# Logic_Analyzer.net
KiCad netlist of a schematic drawn in Altium Designer
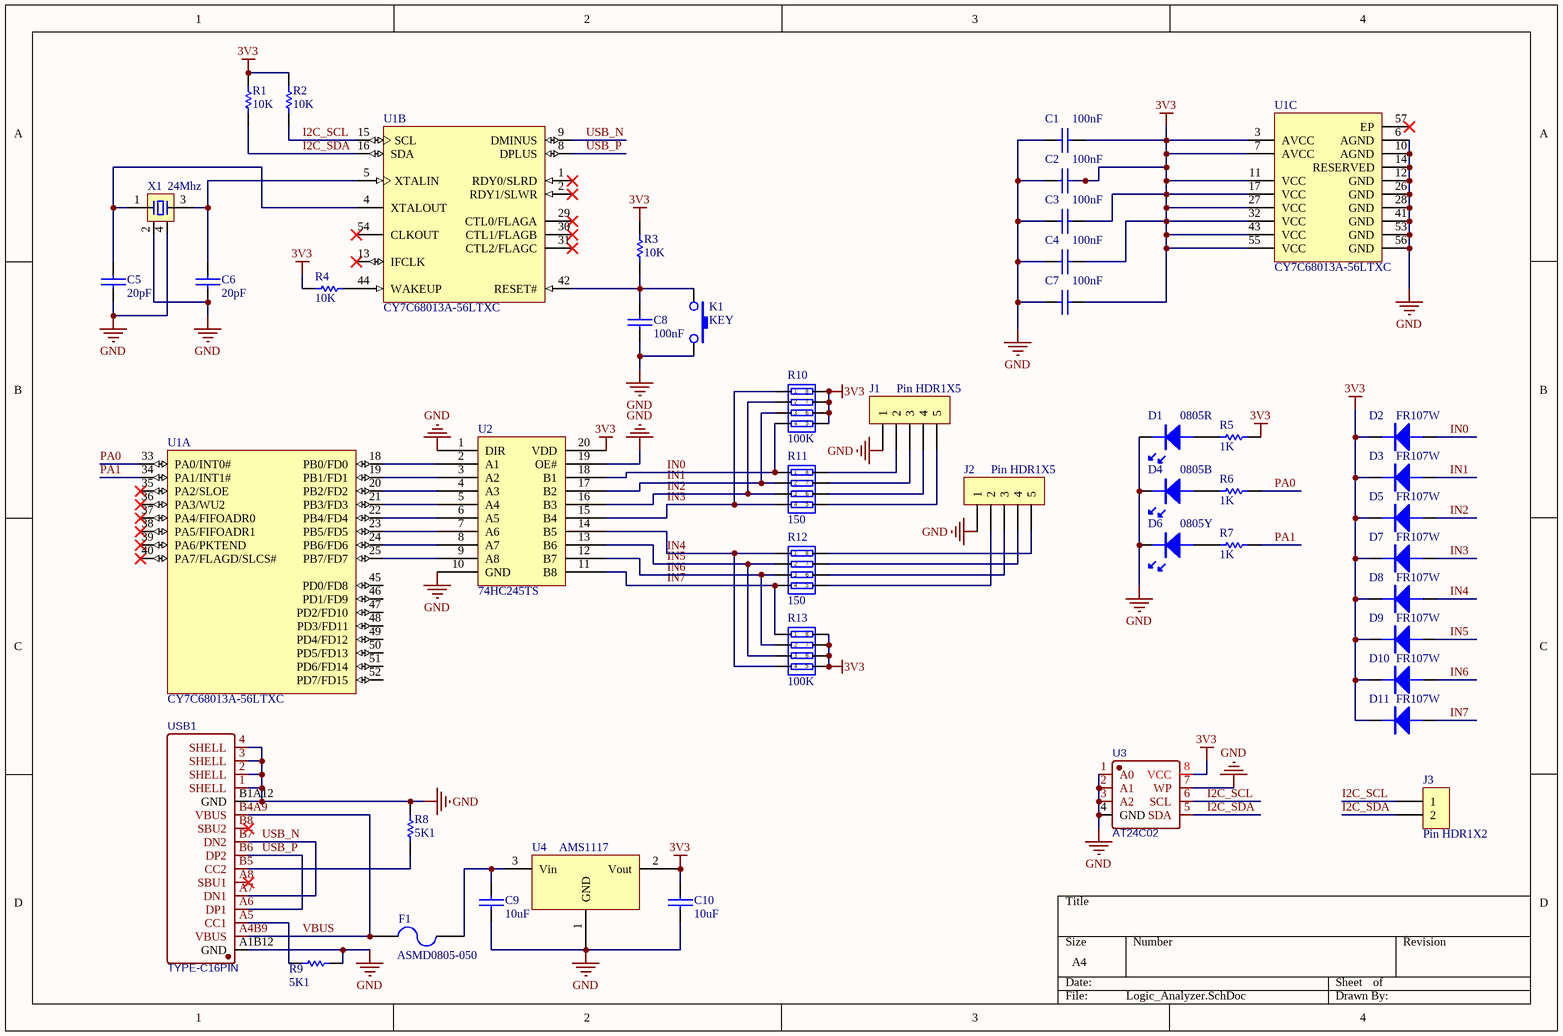
[diagram p0: Logic_Analyzer.SchDoc]

(export (version "E")
  (design (tool "Eeschema 10.0.6"))
  (components
    (comp (ref "C1")
      (value "100nF")
      (footprint "0603C")
      (description "无极性电容")
      (libsource (lib "电容") (part "CAP"))
    )
    (comp (ref "C2")
      (value "100nF")
      (footprint "0603C")
      (description "无极性电容")
      (libsource (lib "电容") (part "CAP"))
    )
    (comp (ref "C3")
      (value "100nF")
      (footprint "0603C")
      (description "无极性电容")
      (libsource (lib "电容") (part "CAP"))
    )
    (comp (ref "C4")
      (value "100nF")
      (footprint "0603C")
      (description "无极性电容")
      (libsource (lib "电容") (part "CAP"))
    )
    (comp (ref "C5")
      (value "20pF")
      (footprint "0603C")
      (description "无极性电容")
      (libsource (lib "电容") (part "CAP"))
    )
    (comp (ref "C6")
      (value "20pF")
      (footprint "0603C")
      (description "无极性电容")
      (libsource (lib "电容") (part "CAP"))
    )
    (comp (ref "C7")
      (value "100nF")
      (footprint "0603C")
      (description "无极性电容")
      (libsource (lib "电容") (part "CAP"))
    )
    (comp (ref "C8")
      (value "100nF")
      (footprint "0603C")
      (description "无极性电容")
      (libsource (lib "电容") (part "CAP"))
    )
    (comp (ref "C9")
      (value "10uF")
      (footprint "0603C")
      (description "无极性电容")
      (libsource (lib "电容") (part "CAP"))
    )
    (comp (ref "C10")
      (value "10uF")
      (footprint "0603C")
      (description "无极性电容")
      (libsource (lib "电容") (part "CAP"))
    )
    (comp (ref "D1") (value "0805R") (footprint "LED-0805R") (libsource (lib "LED") (part "LED")))
    (comp (ref "D2")
      (value "FR107W")
      (footprint "SOD-123")
      (description "普通二极管")
      (libsource (lib "二极管") (part "DIODE"))
    )
    (comp (ref "D3")
      (value "FR107W")
      (footprint "SOD-123")
      (description "普通二极管")
      (libsource (lib "二极管") (part "DIODE"))
    )
    (comp (ref "D4") (value "0805B") (footprint "LED-0805B") (libsource (lib "LED") (part "LED")))
    (comp (ref "D5")
      (value "FR107W")
      (footprint "SOD-123")
      (description "普通二极管")
      (libsource (lib "二极管") (part "DIODE"))
    )
    (comp (ref "D6") (value "0805Y") (footprint "LED-0805Y") (libsource (lib "LED") (part "LED")))
    (comp (ref "D7")
      (value "FR107W")
      (footprint "SOD-123")
      (description "普通二极管")
      (libsource (lib "二极管") (part "DIODE"))
    )
    (comp (ref "D8")
      (value "FR107W")
      (footprint "SOD-123")
      (description "普通二极管")
      (libsource (lib "二极管") (part "DIODE"))
    )
    (comp (ref "D9")
      (value "FR107W")
      (footprint "SOD-123")
      (description "普通二极管")
      (libsource (lib "二极管") (part "DIODE"))
    )
    (comp (ref "D10")
      (value "FR107W")
      (footprint "SOD-123")
      (description "普通二极管")
      (libsource (lib "二极管") (part "DIODE"))
    )
    (comp (ref "D11")
      (value "FR107W")
      (footprint "SOD-123")
      (description "普通二极管")
      (libsource (lib "二极管") (part "DIODE"))
    )
    (comp (ref "F1") (value "ASMD0805-050") (footprint "FUSE-0805") (libsource (lib "保险丝") (part "FUSE")))
    (comp (ref "J1")
      (value "Pin HDR1X5")
      (footprint "Pin HDR1X5/2.54mm-S-SMD")
      (libsource (lib "排针") (part "Pin HDR1X5"))
    )
    (comp (ref "J2")
      (value "Pin HDR1X5")
      (footprint "Pin HDR1X5/2.54mm-S-SMD")
      (libsource (lib "排针") (part "Pin HDR1X5"))
    )
    (comp (ref "J3")
      (value "Pin HDR1X2")
      (footprint "Pin HDR1X2/2.54mm-S")
      (libsource (lib "排针") (part "Pin HDR1X2"))
    )
    (comp (ref "K1")
      (value "KEY")
      (footprint "SW-SMD_L4.0-W2.9-P4.15-EH")
      (libsource (lib "轻触开关") (part "KEY"))
    )
    (comp (ref "R1") (value "10K") (footprint "0603R") (libsource (lib "电阻") (part "RES")))
    (comp (ref "R2") (value "10K") (footprint "0603R") (libsource (lib "电阻") (part "RES")))
    (comp (ref "R3") (value "10K") (footprint "0603R") (libsource (lib "电阻") (part "RES")))
    (comp (ref "R4") (value "10K") (footprint "0603R") (libsource (lib "电阻") (part "RES")))
    (comp (ref "R5") (value "1K") (footprint "0603R") (libsource (lib "电阻") (part "RES")))
    (comp (ref "R6") (value "1K") (footprint "0603R") (libsource (lib "电阻") (part "RES")))
    (comp (ref "R7") (value "1K") (footprint "0603R") (libsource (lib "电阻") (part "RES")))
    (comp (ref "R8") (value "5K1") (footprint "0603R") (libsource (lib "电阻") (part "RES")))
    (comp (ref "R9") (value "5K1") (footprint "0603R") (libsource (lib "电阻") (part "RES")))
    (comp (ref "R10")
      (value "100K")
      (footprint "RES-ARRAY-SMD_0603-8P-L3.2-W1.6-BL")
      (description "网络排阻4R")
      (libsource (lib "电阻") (part "RES_ARRAY*4"))
    )
    (comp (ref "R11")
      (value "150")
      (footprint "RES-ARRAY-SMD_0603-8P-L3.2-W1.6-BL")
      (description "网络排阻4R")
      (libsource (lib "电阻") (part "RES_ARRAY*4"))
    )
    (comp (ref "R12")
      (value "150")
      (footprint "RES-ARRAY-SMD_0603-8P-L3.2-W1.6-BL")
      (description "网络排阻4R")
      (libsource (lib "电阻") (part "RES_ARRAY*4"))
    )
    (comp (ref "R13")
      (value "100K")
      (footprint "RES-ARRAY-SMD_0603-8P-L3.2-W1.6-BL")
      (description "网络排阻4R")
      (libsource (lib "电阻") (part "RES_ARRAY*4"))
    )
    (comp (ref "U1")
      (value "CY7C68013A-56LTXC")
      (footprint "CYP-LTX56-5200X4500TP_M")
      (fields (field (name "MANUFACTURER") "Cypress"))
      (libsource (lib "Cypress USB Controllers") (part "CY7C68013A-56LTXC"))
    )
    (comp (ref "U2") (value "74HC245TS") (footprint "TSSOP20") (libsource (lib "74系列芯片") (part "74HC245TS")))
    (comp (ref "U3")
      (value "AT24C02")
      (footprint "SOP8")
      (fields (field (name "BOM_SUPPLIER PART") "C688857") (field (name "CONTRIBUTOR") "LCSC"))
      (libsource (lib "未分类IC") (part "AT24C02"))
    )
    (comp (ref "U4")
      (value "AMS1117")
      (footprint "SOT223")
      (description "三端稳压芯片")
      (libsource (lib "电源芯片") (part "AMS1117"))
    )
    (comp (ref "USB1")
      (value "TYPE-C16PIN")
      (footprint "USB-C-SMD_TYPE-C16PIN")
      (fields (field (name "BOM_SUPPLIER PART") "C393939") (field (name "CONTRIBUTOR") "LCSC"))
      (libsource (lib "USB") (part "USB-C_16PIN"))
    )
    (comp (ref "X1")
      (value "24Mhz")
      (footprint "OSC 3225-4P")
      (description "4脚无源晶振")
      (libsource (lib "晶振") (part "XTAL-4P"))
    )
  )
  (nets
    (net (code "1") (name "/I2C_SCL") (class "Default")
      (node (ref "J3") (pin "1") (pinfunction "1_1") (pintype "passive"))
      (node (ref "R2") (pin "1") (pinfunction "1_1") (pintype "passive"))
      (node (ref "U1") (pin "15") (pinfunction "SCL_15") (pintype "bidirectional"))
      (node (ref "U3") (pin "6") (pinfunction "SCL_6") (pintype "passive"))
    )
    (net (code "2") (name "/I2C_SDA") (class "Default")
      (node (ref "J3") (pin "2") (pinfunction "2_2") (pintype "passive"))
      (node (ref "R1") (pin "1") (pinfunction "1_1") (pintype "passive"))
      (node (ref "U1") (pin "16") (pinfunction "SDA_16") (pintype "bidirectional"))
      (node (ref "U3") (pin "5") (pinfunction "SDA_5") (pintype "passive"))
    )
    (net (code "3") (name "/IN0") (class "Default")
      (node (ref "D2") (pin "A") (pinfunction "A_A") (pintype "passive"))
      (node (ref "R10") (pin "4") (pinfunction "4_4") (pintype "passive"))
      (node (ref "R11") (pin "1") (pinfunction "1_1") (pintype "passive"))
      (node (ref "U2") (pin "18") (pinfunction "B1_18") (pintype "passive"))
    )
    (net (code "4") (name "/IN1") (class "Default")
      (node (ref "D3") (pin "A") (pinfunction "A_A") (pintype "passive"))
      (node (ref "R10") (pin "3") (pinfunction "3_3") (pintype "passive"))
      (node (ref "R11") (pin "2") (pinfunction "2_2") (pintype "passive"))
      (node (ref "U2") (pin "17") (pinfunction "B2_17") (pintype "passive"))
    )
    (net (code "5") (name "/IN2") (class "Default")
      (node (ref "D5") (pin "A") (pinfunction "A_A") (pintype "passive"))
      (node (ref "R10") (pin "2") (pinfunction "2_2") (pintype "passive"))
      (node (ref "R11") (pin "3") (pinfunction "3_3") (pintype "passive"))
      (node (ref "U2") (pin "16") (pinfunction "B3_16") (pintype "passive"))
    )
    (net (code "6") (name "/IN3") (class "Default")
      (node (ref "D7") (pin "A") (pinfunction "A_A") (pintype "passive"))
      (node (ref "R10") (pin "1") (pinfunction "1_1") (pintype "passive"))
      (node (ref "R11") (pin "4") (pinfunction "4_4") (pintype "passive"))
      (node (ref "U2") (pin "15") (pinfunction "B4_15") (pintype "passive"))
    )
    (net (code "7") (name "/IN4") (class "Default")
      (node (ref "D8") (pin "A") (pinfunction "A_A") (pintype "passive"))
      (node (ref "R12") (pin "1") (pinfunction "1_1") (pintype "passive"))
      (node (ref "R13") (pin "4") (pinfunction "4_4") (pintype "passive"))
      (node (ref "U2") (pin "14") (pinfunction "B5_14") (pintype "passive"))
    )
    (net (code "8") (name "/IN5") (class "Default")
      (node (ref "D9") (pin "A") (pinfunction "A_A") (pintype "passive"))
      (node (ref "R12") (pin "2") (pinfunction "2_2") (pintype "passive"))
      (node (ref "R13") (pin "3") (pinfunction "3_3") (pintype "passive"))
      (node (ref "U2") (pin "13") (pinfunction "B6_13") (pintype "passive"))
    )
    (net (code "9") (name "/IN6") (class "Default")
      (node (ref "D10") (pin "A") (pinfunction "A_A") (pintype "passive"))
      (node (ref "R12") (pin "3") (pinfunction "3_3") (pintype "passive"))
      (node (ref "R13") (pin "2") (pinfunction "2_2") (pintype "passive"))
      (node (ref "U2") (pin "12") (pinfunction "B7_12") (pintype "passive"))
    )
    (net (code "10") (name "/IN7") (class "Default")
      (node (ref "D11") (pin "A") (pinfunction "A_A") (pintype "passive"))
      (node (ref "R12") (pin "4") (pinfunction "4_4") (pintype "passive"))
      (node (ref "R13") (pin "1") (pinfunction "1_1") (pintype "passive"))
      (node (ref "U2") (pin "11") (pinfunction "B8_11") (pintype "passive"))
    )
    (net (code "11") (name "/PA0") (class "Default")
      (node (ref "R6") (pin "1") (pinfunction "1_1") (pintype "passive"))
      (node (ref "U1") (pin "33") (pinfunction "PA0/INT0#_33") (pintype "bidirectional"))
    )
    (net (code "12") (name "/PA1") (class "Default")
      (node (ref "R7") (pin "1") (pinfunction "1_1") (pintype "passive"))
      (node (ref "U1") (pin "34") (pinfunction "PA1/INT1#_34") (pintype "bidirectional"))
    )
    (net (code "13") (name "/USB_N") (class "Default")
      (node (ref "U1") (pin "9") (pinfunction "DMINUS_9") (pintype "bidirectional"))
      (node (ref "USB1") (pin "A7") (pinfunction "DN1_A7") (pintype "passive"))
      (node (ref "USB1") (pin "B7") (pinfunction "DN2_B7") (pintype "passive"))
    )
    (net (code "14") (name "/USB_P") (class "Default")
      (node (ref "U1") (pin "8") (pinfunction "DPLUS_8") (pintype "bidirectional"))
      (node (ref "USB1") (pin "A6") (pinfunction "DP1_A6") (pintype "passive"))
      (node (ref "USB1") (pin "B6") (pinfunction "DP2_B6") (pintype "passive"))
    )
    (net (code "15") (name "/VBUS") (class "Default")
      (node (ref "F1") (pin "1") (pinfunction "1_1") (pintype "passive"))
      (node (ref "USB1") (pin "A4B9") (pinfunction "VBUS_A4B9") (pintype "passive"))
      (node (ref "USB1") (pin "B4A9") (pinfunction "VBUS_B4A9") (pintype "passive"))
    )
    (net (code "16") (name "3V3") (class "Default")
      (node (ref "C1") (pin "1") (pinfunction "1_1") (pintype "passive"))
      (node (ref "C10") (pin "2") (pinfunction "2_2") (pintype "passive"))
      (node (ref "C2") (pin "1") (pinfunction "1_1") (pintype "passive"))
      (node (ref "C3") (pin "1") (pinfunction "1_1") (pintype "passive"))
      (node (ref "C4") (pin "1") (pinfunction "1_1") (pintype "passive"))
      (node (ref "C7") (pin "1") (pinfunction "1_1") (pintype "passive"))
      (node (ref "D10") (pin "K") (pinfunction "K_K") (pintype "passive"))
      (node (ref "D11") (pin "K") (pinfunction "K_K") (pintype "passive"))
      (node (ref "D2") (pin "K") (pinfunction "K_K") (pintype "passive"))
      (node (ref "D3") (pin "K") (pinfunction "K_K") (pintype "passive"))
      (node (ref "D5") (pin "K") (pinfunction "K_K") (pintype "passive"))
      (node (ref "D7") (pin "K") (pinfunction "K_K") (pintype "passive"))
      (node (ref "D8") (pin "K") (pinfunction "K_K") (pintype "passive"))
      (node (ref "D9") (pin "K") (pinfunction "K_K") (pintype "passive"))
      (node (ref "R1") (pin "2") (pinfunction "2_2") (pintype "passive"))
      (node (ref "R10") (pin "5") (pinfunction "5_5") (pintype "passive"))
      (node (ref "R10") (pin "6") (pinfunction "6_6") (pintype "passive"))
      (node (ref "R10") (pin "7") (pinfunction "7_7") (pintype "passive"))
      (node (ref "R10") (pin "8") (pinfunction "8_8") (pintype "passive"))
      (node (ref "R13") (pin "5") (pinfunction "5_5") (pintype "passive"))
      (node (ref "R13") (pin "6") (pinfunction "6_6") (pintype "passive"))
      (node (ref "R13") (pin "7") (pinfunction "7_7") (pintype "passive"))
      (node (ref "R13") (pin "8") (pinfunction "8_8") (pintype "passive"))
      (node (ref "R2") (pin "2") (pinfunction "2_2") (pintype "passive"))
      (node (ref "R3") (pin "2") (pinfunction "2_2") (pintype "passive"))
      (node (ref "R4") (pin "2") (pinfunction "2_2") (pintype "passive"))
      (node (ref "R5") (pin "1") (pinfunction "1_1") (pintype "passive"))
      (node (ref "U1") (pin "11") (pinfunction "VCC_11") (pintype "power_in"))
      (node (ref "U1") (pin "17") (pinfunction "VCC_17") (pintype "power_in"))
      (node (ref "U1") (pin "27") (pinfunction "VCC_27") (pintype "power_in"))
      (node (ref "U1") (pin "3") (pinfunction "AVCC_3") (pintype "power_in"))
      (node (ref "U1") (pin "32") (pinfunction "VCC_32") (pintype "power_in"))
      (node (ref "U1") (pin "43") (pinfunction "VCC_43") (pintype "power_in"))
      (node (ref "U1") (pin "55") (pinfunction "VCC_55") (pintype "power_in"))
      (node (ref "U1") (pin "7") (pinfunction "AVCC_7") (pintype "power_in"))
      (node (ref "U2") (pin "20") (pinfunction "VDD_20") (pintype "passive"))
      (node (ref "U3") (pin "8") (pinfunction "VCC_8") (pintype "passive"))
      (node (ref "U4") (pin "2") (pinfunction "Vout_2") (pintype "passive"))
    )
    (net (code "17") (name "GND") (class "Default")
      (node (ref "C1") (pin "2") (pinfunction "2_2") (pintype "passive"))
      (node (ref "C10") (pin "1") (pinfunction "1_1") (pintype "passive"))
      (node (ref "C2") (pin "2") (pinfunction "2_2") (pintype "passive"))
      (node (ref "C3") (pin "2") (pinfunction "2_2") (pintype "passive"))
      (node (ref "C4") (pin "2") (pinfunction "2_2") (pintype "passive"))
      (node (ref "C5") (pin "1") (pinfunction "1_1") (pintype "passive"))
      (node (ref "C6") (pin "1") (pinfunction "1_1") (pintype "passive"))
      (node (ref "C7") (pin "2") (pinfunction "2_2") (pintype "passive"))
      (node (ref "C8") (pin "1") (pinfunction "1_1") (pintype "passive"))
      (node (ref "C9") (pin "1") (pinfunction "1_1") (pintype "passive"))
      (node (ref "D1") (pin "K") (pinfunction "K_K") (pintype "passive"))
      (node (ref "D4") (pin "K") (pinfunction "K_K") (pintype "passive"))
      (node (ref "D6") (pin "K") (pinfunction "K_K") (pintype "passive"))
      (node (ref "J1") (pin "1") (pinfunction "1_1") (pintype "passive"))
      (node (ref "J2") (pin "1") (pinfunction "1_1") (pintype "passive"))
      (node (ref "K1") (pin "3") (pinfunction "3_3") (pintype "passive"))
      (node (ref "R8") (pin "1") (pinfunction "1_1") (pintype "passive"))
      (node (ref "R9") (pin "1") (pinfunction "1_1") (pintype "passive"))
      (node (ref "U1") (pin "10") (pinfunction "AGND_10") (pintype "power_in"))
      (node (ref "U1") (pin "12") (pinfunction "GND_12") (pintype "power_in"))
      (node (ref "U1") (pin "14") (pinfunction "RESERVED_14") (pintype "power_in"))
      (node (ref "U1") (pin "26") (pinfunction "GND_26") (pintype "power_in"))
      (node (ref "U1") (pin "28") (pinfunction "GND_28") (pintype "power_in"))
      (node (ref "U1") (pin "41") (pinfunction "GND_41") (pintype "power_in"))
      (node (ref "U1") (pin "53") (pinfunction "GND_53") (pintype "power_in"))
      (node (ref "U1") (pin "56") (pinfunction "GND_56") (pintype "power_in"))
      (node (ref "U1") (pin "6") (pinfunction "AGND_6") (pintype "power_in"))
      (node (ref "U2") (pin "1") (pinfunction "DIR_1") (pintype "passive"))
      (node (ref "U2") (pin "10") (pinfunction "GND_10") (pintype "passive"))
      (node (ref "U2") (pin "19") (pinfunction "OE#_19") (pintype "passive"))
      (node (ref "U3") (pin "1") (pinfunction "A0_1") (pintype "passive"))
      (node (ref "U3") (pin "2") (pinfunction "A1_2") (pintype "passive"))
      (node (ref "U3") (pin "3") (pinfunction "A2_3") (pintype "passive"))
      (node (ref "U3") (pin "4") (pinfunction "GND_4") (pintype "passive"))
      (node (ref "U3") (pin "7") (pinfunction "WP_7") (pintype "passive"))
      (node (ref "U4") (pin "1") (pinfunction "GND_1") (pintype "passive"))
      (node (ref "USB1") (pin "1") (pinfunction "SHELL_1") (pintype "passive"))
      (node (ref "USB1") (pin "2") (pinfunction "SHELL_2") (pintype "passive"))
      (node (ref "USB1") (pin "3") (pinfunction "SHELL_3") (pintype "passive"))
      (node (ref "USB1") (pin "4") (pinfunction "SHELL_4") (pintype "passive"))
      (node (ref "USB1") (pin "A1B12") (pinfunction "GND_A1B12") (pintype "passive"))
      (node (ref "USB1") (pin "B1A12") (pinfunction "GND_B1A12") (pintype "passive"))
      (node (ref "X1") (pin "2") (pinfunction "2_2") (pintype "passive"))
      (node (ref "X1") (pin "4") (pinfunction "4_4") (pintype "passive"))
    )
    (net (code "18") (name "Net-(D1-PadA)") (class "Default")
      (node (ref "D1") (pin "A") (pinfunction "A_A") (pintype "passive"))
      (node (ref "R5") (pin "2") (pinfunction "2_2") (pintype "passive"))
    )
    (net (code "19") (name "Net-(D4-PadA)") (class "Default")
      (node (ref "D4") (pin "A") (pinfunction "A_A") (pintype "passive"))
      (node (ref "R6") (pin "2") (pinfunction "2_2") (pintype "passive"))
    )
    (net (code "20") (name "Net-(D6-PadA)") (class "Default")
      (node (ref "D6") (pin "A") (pinfunction "A_A") (pintype "passive"))
      (node (ref "R7") (pin "2") (pinfunction "2_2") (pintype "passive"))
    )
    (net (code "21") (name "Net-(J1-Pad2)") (class "Default")
      (node (ref "J1") (pin "2") (pinfunction "2_2") (pintype "passive"))
      (node (ref "R11") (pin "8") (pinfunction "8_8") (pintype "passive"))
    )
    (net (code "22") (name "Net-(J1-Pad3)") (class "Default")
      (node (ref "J1") (pin "3") (pinfunction "3_3") (pintype "passive"))
      (node (ref "R11") (pin "7") (pinfunction "7_7") (pintype "passive"))
    )
    (net (code "23") (name "Net-(J1-Pad4)") (class "Default")
      (node (ref "J1") (pin "4") (pinfunction "4_4") (pintype "passive"))
      (node (ref "R11") (pin "6") (pinfunction "6_6") (pintype "passive"))
    )
    (net (code "24") (name "Net-(J1-Pad5)") (class "Default")
      (node (ref "J1") (pin "5") (pinfunction "5_5") (pintype "passive"))
      (node (ref "R11") (pin "5") (pinfunction "5_5") (pintype "passive"))
    )
    (net (code "25") (name "Net-(J2-Pad2)") (class "Default")
      (node (ref "J2") (pin "2") (pinfunction "2_2") (pintype "passive"))
      (node (ref "R12") (pin "5") (pinfunction "5_5") (pintype "passive"))
    )
    (net (code "26") (name "Net-(J2-Pad3)") (class "Default")
      (node (ref "J2") (pin "3") (pinfunction "3_3") (pintype "passive"))
      (node (ref "R12") (pin "6") (pinfunction "6_6") (pintype "passive"))
    )
    (net (code "27") (name "Net-(J2-Pad4)") (class "Default")
      (node (ref "J2") (pin "4") (pinfunction "4_4") (pintype "passive"))
      (node (ref "R12") (pin "7") (pinfunction "7_7") (pintype "passive"))
    )
    (net (code "28") (name "Net-(J2-Pad5)") (class "Default")
      (node (ref "J2") (pin "5") (pinfunction "5_5") (pintype "passive"))
      (node (ref "R12") (pin "8") (pinfunction "8_8") (pintype "passive"))
    )
    (net (code "29") (name "Net-(U1A-PB0{slash}FD0)") (class "Default")
      (node (ref "U1") (pin "18") (pinfunction "PB0/FD0_18") (pintype "bidirectional"))
      (node (ref "U2") (pin "2") (pinfunction "A1_2") (pintype "passive"))
    )
    (net (code "30") (name "Net-(U1A-PB1{slash}FD1)") (class "Default")
      (node (ref "U1") (pin "19") (pinfunction "PB1/FD1_19") (pintype "bidirectional"))
      (node (ref "U2") (pin "3") (pinfunction "A2_3") (pintype "passive"))
    )
    (net (code "31") (name "Net-(U1A-PB2{slash}FD2)") (class "Default")
      (node (ref "U1") (pin "20") (pinfunction "PB2/FD2_20") (pintype "bidirectional"))
      (node (ref "U2") (pin "4") (pinfunction "A3_4") (pintype "passive"))
    )
    (net (code "32") (name "Net-(U1A-PB3{slash}FD3)") (class "Default")
      (node (ref "U1") (pin "21") (pinfunction "PB3/FD3_21") (pintype "bidirectional"))
      (node (ref "U2") (pin "5") (pinfunction "A4_5") (pintype "passive"))
    )
    (net (code "33") (name "Net-(U1A-PB4{slash}FD4)") (class "Default")
      (node (ref "U1") (pin "22") (pinfunction "PB4/FD4_22") (pintype "bidirectional"))
      (node (ref "U2") (pin "6") (pinfunction "A5_6") (pintype "passive"))
    )
    (net (code "34") (name "Net-(U1A-PB5{slash}FD5)") (class "Default")
      (node (ref "U1") (pin "23") (pinfunction "PB5/FD5_23") (pintype "bidirectional"))
      (node (ref "U2") (pin "7") (pinfunction "A6_7") (pintype "passive"))
    )
    (net (code "35") (name "Net-(U1A-PB6{slash}FD6)") (class "Default")
      (node (ref "U1") (pin "24") (pinfunction "PB6/FD6_24") (pintype "bidirectional"))
      (node (ref "U2") (pin "8") (pinfunction "A7_8") (pintype "passive"))
    )
    (net (code "36") (name "Net-(U1A-PB7{slash}FD7)") (class "Default")
      (node (ref "U1") (pin "25") (pinfunction "PB7/FD7_25") (pintype "bidirectional"))
      (node (ref "U2") (pin "9") (pinfunction "A8_9") (pintype "passive"))
    )
    (net (code "37") (name "Net-(U1B-RESET#)") (class "Default")
      (node (ref "C8") (pin "2") (pinfunction "2_2") (pintype "passive"))
      (node (ref "K1") (pin "1") (pinfunction "1_1") (pintype "passive"))
      (node (ref "R3") (pin "1") (pinfunction "1_1") (pintype "passive"))
      (node (ref "U1") (pin "42") (pinfunction "RESET#_42") (pintype "input"))
    )
    (net (code "38") (name "Net-(U1B-WAKEUP)") (class "Default")
      (node (ref "R4") (pin "1") (pinfunction "1_1") (pintype "passive"))
      (node (ref "U1") (pin "44") (pinfunction "WAKEUP_44") (pintype "input"))
    )
    (net (code "39") (name "Net-(U1B-XTALIN)") (class "Default")
      (node (ref "C6") (pin "2") (pinfunction "2_2") (pintype "passive"))
      (node (ref "U1") (pin "5") (pinfunction "XTALIN_5") (pintype "input"))
      (node (ref "X1") (pin "3") (pinfunction "3_3") (pintype "passive"))
    )
    (net (code "40") (name "Net-(U1B-XTALOUT)") (class "Default")
      (node (ref "C5") (pin "2") (pinfunction "2_2") (pintype "passive"))
      (node (ref "U1") (pin "4") (pinfunction "XTALOUT_4") (pintype "passive"))
      (node (ref "X1") (pin "1") (pinfunction "1_1") (pintype "passive"))
    )
    (net (code "41") (name "Net-(U4-Vin)") (class "Default")
      (node (ref "C9") (pin "2") (pinfunction "2_2") (pintype "passive"))
      (node (ref "F1") (pin "2") (pinfunction "2_2") (pintype "passive"))
      (node (ref "U4") (pin "3") (pinfunction "Vin_3") (pintype "passive"))
    )
    (net (code "42") (name "Net-(USB1-CC1)") (class "Default")
      (node (ref "R9") (pin "2") (pinfunction "2_2") (pintype "passive"))
      (node (ref "USB1") (pin "A5") (pinfunction "CC1_A5") (pintype "passive"))
    )
    (net (code "43") (name "Net-(USB1-CC2)") (class "Default")
      (node (ref "R8") (pin "2") (pinfunction "2_2") (pintype "passive"))
      (node (ref "USB1") (pin "B5") (pinfunction "CC2_B5") (pintype "passive"))
    )
    (net (code "44") (name "unconnected-(U1A-PA2{slash}SLOE-Pad35)") (class "Default")
      (node (ref "U1") (pin "35") (pinfunction "PA2/SLOE_35") (pintype "bidirectional+no_connect"))
    )
    (net (code "45") (name "unconnected-(U1A-PA3{slash}WU2-Pad36)") (class "Default")
      (node (ref "U1") (pin "36") (pinfunction "PA3/WU2_36") (pintype "bidirectional+no_connect"))
    )
    (net (code "46") (name "unconnected-(U1A-PA4{slash}FIFOADR0-Pad37)") (class "Default")
      (node (ref "U1") (pin "37") (pinfunction "PA4/FIFOADR0_37") (pintype "bidirectional+no_connect"))
    )
    (net (code "47") (name "unconnected-(U1A-PA5{slash}FIFOADR1-Pad38)") (class "Default")
      (node (ref "U1") (pin "38") (pinfunction "PA5/FIFOADR1_38") (pintype "bidirectional+no_connect"))
    )
    (net (code "48") (name "unconnected-(U1A-PA6{slash}PKTEND-Pad39)") (class "Default")
      (node (ref "U1") (pin "39") (pinfunction "PA6/PKTEND_39") (pintype "bidirectional+no_connect"))
    )
    (net (code "49") (name "unconnected-(U1A-PA7{slash}FLAGD{slash}SLCS#-Pad40)") (class "Default")
      (node (ref "U1") (pin "40") (pinfunction "PA7/FLAGD/SLCS#_40") (pintype "bidirectional+no_connect"))
    )
    (net (code "50") (name "unconnected-(U1A-PD0{slash}FD8-Pad45)") (class "Default")
      (node (ref "U1") (pin "45") (pinfunction "PD0/FD8_45") (pintype "bidirectional"))
    )
    (net (code "51") (name "unconnected-(U1A-PD1{slash}FD9-Pad46)") (class "Default")
      (node (ref "U1") (pin "46") (pinfunction "PD1/FD9_46") (pintype "bidirectional"))
    )
    (net (code "52") (name "unconnected-(U1A-PD2{slash}FD10-Pad47)") (class "Default")
      (node (ref "U1") (pin "47") (pinfunction "PD2/FD10_47") (pintype "bidirectional"))
    )
    (net (code "53") (name "unconnected-(U1A-PD3{slash}FD11-Pad48)") (class "Default")
      (node (ref "U1") (pin "48") (pinfunction "PD3/FD11_48") (pintype "bidirectional"))
    )
    (net (code "54") (name "unconnected-(U1A-PD4{slash}FD12-Pad49)") (class "Default")
      (node (ref "U1") (pin "49") (pinfunction "PD4/FD12_49") (pintype "bidirectional"))
    )
    (net (code "55") (name "unconnected-(U1A-PD5{slash}FD13-Pad50)") (class "Default")
      (node (ref "U1") (pin "50") (pinfunction "PD5/FD13_50") (pintype "bidirectional"))
    )
    (net (code "56") (name "unconnected-(U1A-PD6{slash}FD14-Pad51)") (class "Default")
      (node (ref "U1") (pin "51") (pinfunction "PD6/FD14_51") (pintype "bidirectional"))
    )
    (net (code "57") (name "unconnected-(U1A-PD7{slash}FD15-Pad52)") (class "Default")
      (node (ref "U1") (pin "52") (pinfunction "PD7/FD15_52") (pintype "bidirectional"))
    )
    (net (code "58") (name "unconnected-(U1B-CLKOUT-Pad54)") (class "Default")
      (node (ref "U1") (pin "54") (pinfunction "CLKOUT_54") (pintype "tri_state+no_connect"))
    )
    (net (code "59") (name "unconnected-(U1B-CTL0{slash}FLAGA-Pad29)") (class "Default")
      (node (ref "U1") (pin "29") (pinfunction "CTL0/FLAGA_29") (pintype "tri_state+no_connect"))
    )
    (net (code "60") (name "unconnected-(U1B-CTL1{slash}FLAGB-Pad30)") (class "Default")
      (node (ref "U1") (pin "30") (pinfunction "CTL1/FLAGB_30") (pintype "tri_state+no_connect"))
    )
    (net (code "61") (name "unconnected-(U1B-CTL2{slash}FLAGC-Pad31)") (class "Default")
      (node (ref "U1") (pin "31") (pinfunction "CTL2/FLAGC_31") (pintype "tri_state+no_connect"))
    )
    (net (code "62") (name "unconnected-(U1B-IFCLK-Pad13)") (class "Default")
      (node (ref "U1") (pin "13") (pinfunction "IFCLK_13") (pintype "bidirectional+no_connect"))
    )
    (net (code "63") (name "unconnected-(U1B-RDY0{slash}SLRD-Pad1)") (class "Default")
      (node (ref "U1") (pin "1") (pinfunction "RDY0/SLRD_1") (pintype "input+no_connect"))
    )
    (net (code "64") (name "unconnected-(U1B-RDY1{slash}SLWR-Pad2)") (class "Default")
      (node (ref "U1") (pin "2") (pinfunction "RDY1/SLWR_2") (pintype "input+no_connect"))
    )
    (net (code "65") (name "unconnected-(U1C-EP-Pad57)") (class "Default")
      (node (ref "U1") (pin "57") (pinfunction "EP_57") (pintype "passive+no_connect"))
    )
    (net (code "66") (name "unconnected-(USB1-SBU1-PadA8)") (class "Default")
      (node (ref "USB1") (pin "A8") (pinfunction "SBU1_A8") (pintype "passive+no_connect"))
    )
    (net (code "67") (name "unconnected-(USB1-SBU2-PadB8)") (class "Default")
      (node (ref "USB1") (pin "B8") (pinfunction "SBU2_B8") (pintype "passive+no_connect"))
    )
  )
)
